# SoC.net
KiCad netlist of a schematic drawn in Altium Designer
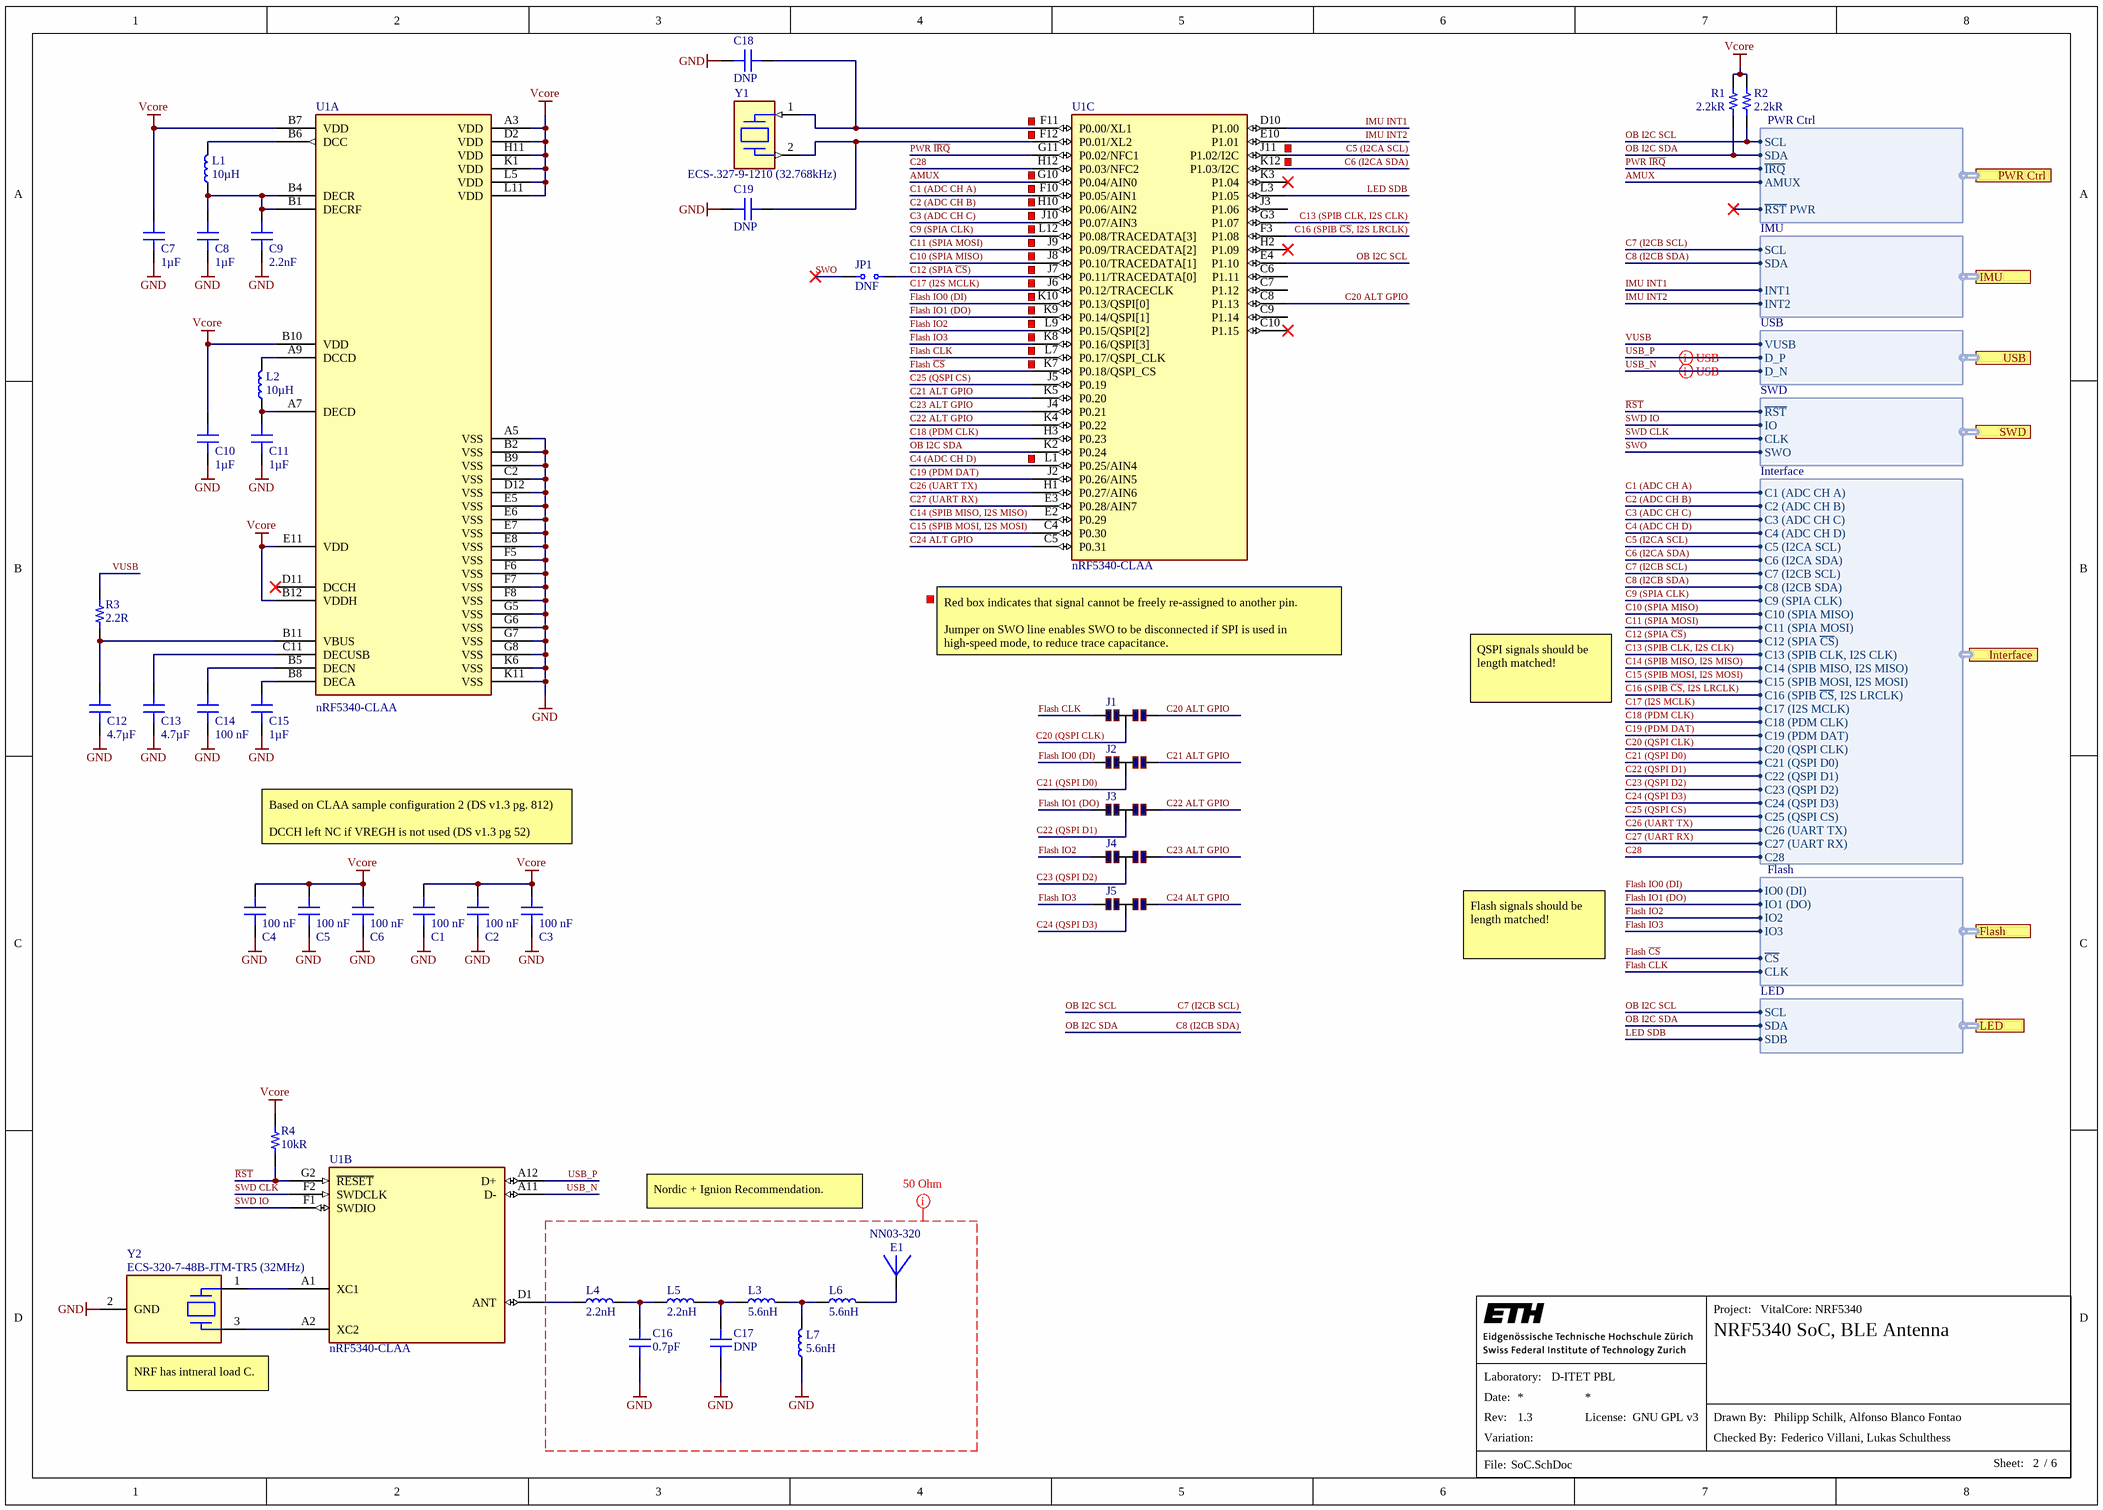
[diagram p0: SoC.SchDoc]

(export (version "E")
  (design (tool "Eeschema 10.0.6"))
  (components
    (comp (ref "C1")
      (value "100 nF")
      (footprint "VC_PCBLib:CAP_0201")
      (description "CAP CER 0.1UF 10V X5R 0201")
      (fields
        (field (name "MANUFACTURER") "Murata")
        (field (name "MANUFACTURER PART NUMBER") "GRM033Z71A104KE14D")
      )
      (libsource (lib "VC_SchematicLib") (part "CAP_0201_100n_10V"))
    )
    (comp (ref "C2")
      (value "100 nF")
      (footprint "VC_PCBLib:CAP_0201")
      (description "CAP CER 0.1UF 10V X5R 0201")
      (fields
        (field (name "MANUFACTURER") "Murata")
        (field (name "MANUFACTURER PART NUMBER") "GRM033Z71A104KE14D")
      )
      (libsource (lib "VC_SchematicLib") (part "CAP_0201_100n_10V"))
    )
    (comp (ref "C3")
      (value "100 nF")
      (footprint "VC_PCBLib:CAP_0201")
      (description "CAP CER 0.1UF 10V X5R 0201")
      (fields
        (field (name "MANUFACTURER") "Murata")
        (field (name "MANUFACTURER PART NUMBER") "GRM033Z71A104KE14D")
      )
      (libsource (lib "VC_SchematicLib") (part "CAP_0201_100n_10V"))
    )
    (comp (ref "C4")
      (value "100 nF")
      (footprint "VC_PCBLib:CAP_0201")
      (description "CAP CER 0.1UF 10V X5R 0201")
      (fields
        (field (name "MANUFACTURER") "Murata")
        (field (name "MANUFACTURER PART NUMBER") "GRM033Z71A104KE14D")
      )
      (libsource (lib "VC_SchematicLib") (part "CAP_0201_100n_10V"))
    )
    (comp (ref "C5")
      (value "100 nF")
      (footprint "VC_PCBLib:CAP_0201")
      (description "CAP CER 0.1UF 10V X5R 0201")
      (fields
        (field (name "MANUFACTURER") "Murata")
        (field (name "MANUFACTURER PART NUMBER") "GRM033Z71A104KE14D")
      )
      (libsource (lib "VC_SchematicLib") (part "CAP_0201_100n_10V"))
    )
    (comp (ref "C6")
      (value "100 nF")
      (footprint "VC_PCBLib:CAP_0201")
      (description "CAP CER 0.1UF 10V X5R 0201")
      (fields
        (field (name "MANUFACTURER") "Murata")
        (field (name "MANUFACTURER PART NUMBER") "GRM033Z71A104KE14D")
      )
      (libsource (lib "VC_SchematicLib") (part "CAP_0201_100n_10V"))
    )
    (comp (ref "C7")
      (value "1µF")
      (footprint "VC_PCBLib:CAP_0201")
      (description "CAP CER 1UF 10V X6S")
      (fields
        (field (name "MANUFACTURER") "Murata")
        (field (name "MANUFACTURER PART NUMBER") "GRM033C81A105ME05D")
      )
      (libsource (lib "VC_SchematicLib") (part "CAP_0201_1u_10V"))
    )
    (comp (ref "C8")
      (value "1µF")
      (footprint "VC_PCBLib:CAP_0201")
      (description "CAP CER 1UF 10V X6S")
      (fields
        (field (name "MANUFACTURER") "Murata")
        (field (name "MANUFACTURER PART NUMBER") "GRM033C81A105ME05D")
      )
      (libsource (lib "VC_SchematicLib") (part "CAP_0201_1u_10V"))
    )
    (comp (ref "C9")
      (value "2.2nF")
      (footprint "VC_PCBLib:CAP_0201")
      (description "CAP CER 2.2NF 16V X7R 0201")
      (fields
        (field (name "MANUFACTURER") "Murata")
        (field (name "MANUFACTURER PART NUMBER") "GRM033R71C222KA88D")
      )
      (libsource (lib "VC_SchematicLib") (part "CAP_0201_2.2n_16V"))
    )
    (comp (ref "C10")
      (value "1µF")
      (footprint "VC_PCBLib:CAP_0201")
      (description "CAP CER 1UF 10V X6S")
      (fields
        (field (name "MANUFACTURER") "Murata")
        (field (name "MANUFACTURER PART NUMBER") "GRM033C81A105ME05D")
      )
      (libsource (lib "VC_SchematicLib") (part "CAP_0201_1u_10V"))
    )
    (comp (ref "C11")
      (value "1µF")
      (footprint "VC_PCBLib:CAP_0201")
      (description "CAP CER 1UF 10V X6S")
      (fields
        (field (name "MANUFACTURER") "Murata")
        (field (name "MANUFACTURER PART NUMBER") "GRM033C81A105ME05D")
      )
      (libsource (lib "VC_SchematicLib") (part "CAP_0201_1u_10V"))
    )
    (comp (ref "C12")
      (value "4.7µF")
      (footprint "VC_PCBLib:CAP_0402")
      (description "CAP CER 4.7UF 16V X5R 0402")
      (fields
        (field (name "MANUFACTURER") "Kyocera AVX")
        (field (name "MANUFACTURER PART NUMBER") "0402YD475MAT2A")
      )
      (libsource (lib "VC_SchematicLib") (part "CAP_0402_4.7u_16V"))
    )
    (comp (ref "C13")
      (value "4.7µF")
      (footprint "VC_PCBLib:CAP_0402")
      (description "CAP CER 4.7UF 16V X5R 0402")
      (fields
        (field (name "MANUFACTURER") "Kyocera AVX")
        (field (name "MANUFACTURER PART NUMBER") "0402YD475MAT2A")
      )
      (libsource (lib "VC_SchematicLib") (part "CAP_0402_4.7u_16V"))
    )
    (comp (ref "C14")
      (value "100 nF")
      (footprint "VC_PCBLib:CAP_0201")
      (description "CAP CER 0.1UF 10V X5R 0201")
      (fields
        (field (name "MANUFACTURER") "Murata")
        (field (name "MANUFACTURER PART NUMBER") "GRM033Z71A104KE14D")
      )
      (libsource (lib "VC_SchematicLib") (part "CAP_0201_100n_10V"))
    )
    (comp (ref "C15")
      (value "1µF")
      (footprint "VC_PCBLib:CAP_0201")
      (description "CAP CER 1UF 10V X6S")
      (fields
        (field (name "MANUFACTURER") "Murata")
        (field (name "MANUFACTURER PART NUMBER") "GRM033C81A105ME05D")
      )
      (libsource (lib "VC_SchematicLib") (part "CAP_0201_1u_10V"))
    )
    (comp (ref "C16")
      (value "0.7pF")
      (footprint "VC_PCBLib:CAP_0201")
      (description "CAP RF CER 0.7PF 25V C0G 0201")
      (fields
        (field (name "MANUFACTURER") "Murata")
        (field (name "MANUFACTURER PART NUMBER") "GJM0335C1ER70BB01D")
      )
      (libsource (lib "VC_SchematicLib") (part "CAP_RF_0201_0.7pF"))
    )
    (comp (ref "C17")
      (value "DNP")
      (footprint "VC_PCBLib:CAP_0201_DNP")
      (description "CAP CER DNP 0201")
      (libsource (lib "VC_SchematicLib") (part "CAP_0201_DNP"))
    )
    (comp (ref "C18")
      (value "DNP")
      (footprint "VC_PCBLib:CAP_0201_DNP")
      (description "CAP CER DNP 0201")
      (libsource (lib "VC_SchematicLib") (part "CAP_0201_DNP"))
    )
    (comp (ref "C19")
      (value "DNP")
      (footprint "VC_PCBLib:CAP_0201_DNP")
      (description "CAP CER DNP 0201")
      (libsource (lib "VC_SchematicLib") (part "CAP_0201_DNP"))
    )
    (comp (ref "E1")
      (value "NN03-320")
      (footprint "VC_PCBLib:NN03-320")
      (description "Integrated Chip Antenna")
      (fields (field (name "MANUFACTURER") "Fractus Antennas"))
      (libsource (lib "VC_SchematicLib") (part "NN03-320"))
    )
    (comp (ref "J1")
      (value "Solder Jumper")
      (footprint "VC_PcbLib:JMP_0201_3WAY")
      (description "Solder Jumper 3 Pads")
      (fields
        (field (name "MANUFACTURER PART NUMBER") "ERJ-1GN0R00C")
        (field (name "MANUFACTURER") "Panasonic")
      )
      (libsource (lib "VC_SchematicLib") (part "JMP_0201_3WAY"))
    )
    (comp (ref "J2")
      (value "Solder Jumper")
      (footprint "VC_PcbLib:JMP_0201_3WAY")
      (description "Solder Jumper 3 Pads")
      (fields
        (field (name "MANUFACTURER PART NUMBER") "ERJ-1GN0R00C")
        (field (name "MANUFACTURER") "Panasonic")
      )
      (libsource (lib "VC_SchematicLib") (part "JMP_0201_3WAY"))
    )
    (comp (ref "J3")
      (value "Solder Jumper")
      (footprint "VC_PcbLib:JMP_0201_3WAY")
      (description "Solder Jumper 3 Pads")
      (fields
        (field (name "MANUFACTURER PART NUMBER") "ERJ-1GN0R00C")
        (field (name "MANUFACTURER") "Panasonic")
      )
      (libsource (lib "VC_SchematicLib") (part "JMP_0201_3WAY"))
    )
    (comp (ref "J4")
      (value "Solder Jumper")
      (footprint "VC_PcbLib:JMP_0201_3WAY")
      (description "Solder Jumper 3 Pads")
      (fields
        (field (name "MANUFACTURER PART NUMBER") "ERJ-1GN0R00C")
        (field (name "MANUFACTURER") "Panasonic")
      )
      (libsource (lib "VC_SchematicLib") (part "JMP_0201_3WAY"))
    )
    (comp (ref "J5")
      (value "Solder Jumper")
      (footprint "VC_PcbLib:JMP_0201_3WAY")
      (description "Solder Jumper 3 Pads")
      (fields
        (field (name "MANUFACTURER PART NUMBER") "ERJ-1GN0R00C")
        (field (name "MANUFACTURER") "Panasonic")
      )
      (libsource (lib "VC_SchematicLib") (part "JMP_0201_3WAY"))
    )
    (comp (ref "JP1")
      (value "DNF")
      (footprint "VC_PCBLib:JMP_0201")
      (description "JMP 0201 NO TRACE DNF")
      (libsource (lib "VC_SchematicLib") (part "JMP_0201_DNF"))
    )
    (comp (ref "L1")
      (value "10µH")
      (footprint "VC_PCBLib:IND_0603")
      (description "L 10uH 300mA 0603")
      (fields
        (field (name "MANUFACTURER") "Murata")
        (field (name "MANUFACTURER PART NUMBER") "LQM18DN100M70L")
      )
      (libsource (lib "VC_SchematicLib") (part "L_0603_10uH_300mA"))
    )
    (comp (ref "L2")
      (value "10µH")
      (footprint "VC_PCBLib:IND_0603")
      (description "L 10uH 300mA 0603")
      (fields
        (field (name "MANUFACTURER") "Murata")
        (field (name "MANUFACTURER PART NUMBER") "LQM18DN100M70L")
      )
      (libsource (lib "VC_SchematicLib") (part "L_0603_10uH_300mA"))
    )
    (comp (ref "L3")
      (value "5.6nH")
      (footprint "VC_PCBLib:IND_0201_MURATA_LQW03AW")
      (description "L 5.6nH RF 0201")
      (fields
        (field (name "MANUFACTURER") "Murata")
        (field (name "MANUFACTURER PART NUMBER") "LQW03AW5N6J00D")
      )
      (libsource (lib "VC_SchematicLib") (part "L_RF_0201_5.6nH"))
    )
    (comp (ref "L4")
      (value "2.2nH")
      (footprint "VC_PCBLib:IND_0201_MURATA_LQW03AW")
      (description "L 2.2nH RF 0201")
      (fields
        (field (name "MANUFACTURER") "Murata")
        (field (name "MANUFACTURER PART NUMBER") "LQP03HQ2N2B02D")
      )
      (libsource (lib "VC_SchematicLib") (part "L_RF_0201_2.2nH"))
    )
    (comp (ref "L5")
      (value "2.2nH")
      (footprint "VC_PCBLib:IND_0201_MURATA_LQW03AW")
      (description "L 2.2nH RF 0201")
      (fields
        (field (name "MANUFACTURER") "Murata")
        (field (name "MANUFACTURER PART NUMBER") "LQP03HQ2N2B02D")
      )
      (libsource (lib "VC_SchematicLib") (part "L_RF_0201_2.2nH"))
    )
    (comp (ref "L6")
      (value "5.6nH")
      (footprint "VC_PCBLib:IND_0201_MURATA_LQW03AW")
      (description "L 5.6nH RF 0201")
      (fields
        (field (name "MANUFACTURER") "Murata")
        (field (name "MANUFACTURER PART NUMBER") "LQW03AW5N6J00D")
      )
      (libsource (lib "VC_SchematicLib") (part "L_RF_0201_5.6nH"))
    )
    (comp (ref "L7")
      (value "5.6nH")
      (footprint "VC_PCBLib:IND_0201_MURATA_LQW03AW")
      (description "L 5.6nH RF 0201")
      (fields
        (field (name "MANUFACTURER") "Murata")
        (field (name "MANUFACTURER PART NUMBER") "LQW03AW5N6J00D")
      )
      (libsource (lib "VC_SchematicLib") (part "L_RF_0201_5.6nH"))
    )
    (comp (ref "R1")
      (value "2.2kR")
      (footprint "VC_PCBLib:RES_0201")
      (description "R 2.2K 1% 50mW 0201")
      (fields
        (field (name "MANUFACTURER") "Panasonic")
        (field (name "MANUFACTURER PART NUMBER") "ERJ-1GNF2201C")
      )
      (libsource (lib "VC_SchematicLib") (part "R_0201_2.2K"))
    )
    (comp (ref "R2")
      (value "2.2kR")
      (footprint "VC_PCBLib:RES_0201")
      (description "R 2.2K 1% 50mW 0201")
      (fields
        (field (name "MANUFACTURER") "Panasonic")
        (field (name "MANUFACTURER PART NUMBER") "ERJ-1GNF2201C")
      )
      (libsource (lib "VC_SchematicLib") (part "R_0201_2.2K"))
    )
    (comp (ref "R3")
      (value "2.2R")
      (footprint "VC_PCBLib:RES_0201")
      (description "R 2.2R 1% 50mW 0201")
      (fields
        (field (name "MANUFACTURER") "Yageo")
        (field (name "MANUFACTURER PART NUMBER") "RC0201FR-072R2L")
      )
      (libsource (lib "VC_SchematicLib") (part "R_0201_2.2R"))
    )
    (comp (ref "R4")
      (value "10kR")
      (footprint "VC_PCBLib:RES_0201")
      (description "R 10K 1% 50mW 0201")
      (fields
        (field (name "MANUFACTURER") "Panasonic")
        (field (name "MANUFACTURER PART NUMBER") "ERJ-1GNF1002C")
      )
      (libsource (lib "VC_SchematicLib") (part "R_0201_10K"))
    )
    (comp (ref "U1")
      (value "nRF5340-CLAA")
      (footprint "VC_PCBLib:NRF5340_WLCSP")
      (description "Multi-protocol Bluetooth Low Energy, IEEE 802.15.4, ANT and 2.4GHz proprietary system-on-chip")
      (fields
        (field (name "MANUFACTURER PART NUMBER") "NRF5340-CLAA-R7")
        (field (name "MANUFACTURER") "Nordic")
      )
      (libsource (lib "VC_SchematicLib") (part "nRF5340-CLAA"))
    )
    (comp (ref "Y1")
      (value "ECS-.327-9-1210 (32.768kHz)")
      (footprint "VC_PCBLib:Y_ECX-1210")
      (description "Crystal 32.768KHZ 9PFSMD ECX-1210 Khz Crystal 32.768KHZ 20PPM 90K Ohm -40C ~ 85C 2-SMD")
      (fields
        (field (name "MANUFACTURER") "ECS International")
        (field (name "MANUFACTURER PART NUMBER") "ECS-.327-9-1210-TR")
      )
      (libsource (lib "VC_SchematicLib") (part "Y_ECS-327-9-1210"))
    )
    (comp (ref "Y2")
      (value "ECS-320-7-48B-JTM-TR5 (32MHz)")
      (footprint "VC_PCBLib:Y_ECX-1048")
      (description "Crystal 32MHz 7pF ±20ppm ±20ppm 4-Pin Ultraminiature CSMD T/R")
      (fields
        (field (name "MANUFACTURER") "ECS International")
        (field (name "MANUFACTURER PART NUMBER") "ECS-320-7-48B-JTM-TR5")
      )
      (libsource (lib "VC_SchematicLib") (part "Y_ECS-320-7-48B-JTM-TR5"))
    )
  )
  (nets
    (net (code "9") (name "/AMUX") (class "Default")
      (node (ref "U1") (pin "G10") (pinfunction "P0.04/AIN0_G10") (pintype "bidirectional"))
    )
    (net (code "10") (name "/C1 (ADC CH A)") (class "Default")
      (node (ref "U1") (pin "F10") (pinfunction "P0.05/AIN1_F10") (pintype "bidirectional"))
    )
    (net (code "11") (name "/C2 (ADC CH B)") (class "Default")
      (node (ref "U1") (pin "H10") (pinfunction "P0.06/AIN2_H10") (pintype "bidirectional"))
    )
    (net (code "12") (name "/C3 (ADC CH C)") (class "Default")
      (node (ref "U1") (pin "J10") (pinfunction "P0.07/AIN3_J10") (pintype "bidirectional"))
    )
    (net (code "13") (name "/C4 (ADC CH D)") (class "Default")
      (node (ref "U1") (pin "L1") (pinfunction "P0.25/AIN4_L1") (pintype "bidirectional"))
    )
    (net (code "14") (name "/C5 (I2CA SCL)") (class "Default")
      (node (ref "U1") (pin "J11") (pinfunction "P1.02/I2C_J11") (pintype "bidirectional"))
    )
    (net (code "15") (name "/C6 (I2CA SDA)") (class "Default")
      (node (ref "U1") (pin "K12") (pinfunction "P1.03/I2C_K12") (pintype "bidirectional"))
    )
    (net (code "16") (name "/C7 (I2CB SCL)") (class "Default")
      (node (ref "R2") (pin "1") (pinfunction "1_1") (pintype "passive"))
      (node (ref "U1") (pin "E4") (pinfunction "P1.10_E4") (pintype "bidirectional"))
    )
    (net (code "17") (name "/C8 (I2CB SDA)") (class "Default")
      (node (ref "R1") (pin "2") (pinfunction "2_2") (pintype "passive"))
      (node (ref "U1") (pin "K2") (pinfunction "P0.24_K2") (pintype "bidirectional"))
    )
    (net (code "18") (name "/C9 (SPIA CLK)") (class "Default")
      (node (ref "U1") (pin "L12") (pinfunction "P0.08/TRACEDATA[3]_L12") (pintype "bidirectional"))
    )
    (net (code "19") (name "/C10 (SPIA MISO)") (class "Default")
      (node (ref "U1") (pin "J8") (pinfunction "P0.10/TRACEDATA[1]_J8") (pintype "bidirectional"))
    )
    (net (code "20") (name "/C11 (SPIA MOSI)") (class "Default")
      (node (ref "U1") (pin "J9") (pinfunction "P0.09/TRACEDATA[2]_J9") (pintype "bidirectional"))
    )
    (net (code "21") (name "/C12 (SPIA ~{CS})") (class "Default")
      (node (ref "JP1") (pin "2") (pinfunction "2_2") (pintype "passive"))
      (node (ref "U1") (pin "J7") (pinfunction "P0.11/TRACEDATA[0]_J7") (pintype "bidirectional"))
    )
    (net (code "22") (name "/C13 (SPIB CLK, I2S CLK)") (class "Default")
      (node (ref "U1") (pin "G3") (pinfunction "P1.07_G3") (pintype "bidirectional"))
    )
    (net (code "23") (name "/C14 (SPIB MISO, I2S MISO)") (class "Default")
      (node (ref "U1") (pin "E2") (pinfunction "P0.29_E2") (pintype "bidirectional"))
    )
    (net (code "24") (name "/C15 (SPIB MOSI, I2S MOSI)") (class "Default")
      (node (ref "U1") (pin "C4") (pinfunction "P0.30_C4") (pintype "bidirectional"))
    )
    (net (code "25") (name "/C16 (SPIB ~{CS}, I2S LRCLK)") (class "Default")
      (node (ref "U1") (pin "F3") (pinfunction "P1.08_F3") (pintype "bidirectional"))
    )
    (net (code "26") (name "/C17 (I2S MCLK)") (class "Default")
      (node (ref "U1") (pin "J6") (pinfunction "P0.12/TRACECLK_J6") (pintype "bidirectional"))
    )
    (net (code "27") (name "/C18 (PDM CLK)") (class "Default")
      (node (ref "U1") (pin "H3") (pinfunction "P0.23_H3") (pintype "bidirectional"))
    )
    (net (code "28") (name "/C19 (PDM DAT)") (class "Default")
      (node (ref "U1") (pin "J2") (pinfunction "P0.26/AIN5_J2") (pintype "bidirectional"))
    )
    (net (code "29") (name "/C20 (QSPI CLK)") (class "Default")
      (node (ref "J1") (pin "2") (pinfunction "2_2") (pintype "passive"))
    )
    (net (code "30") (name "/C20 ALT GPIO") (class "Default")
      (node (ref "J1") (pin "3") (pinfunction "3_3") (pintype "passive"))
      (node (ref "U1") (pin "C8") (pinfunction "P1.13_C8") (pintype "bidirectional"))
    )
    (net (code "31") (name "/C21 (QSPI D0)") (class "Default")
      (node (ref "J2") (pin "2") (pinfunction "2_2") (pintype "passive"))
    )
    (net (code "32") (name "/C21 ALT GPIO") (class "Default")
      (node (ref "J2") (pin "3") (pinfunction "3_3") (pintype "passive"))
      (node (ref "U1") (pin "K5") (pinfunction "P0.20_K5") (pintype "bidirectional"))
    )
    (net (code "33") (name "/C22 (QSPI D1)") (class "Default")
      (node (ref "J3") (pin "2") (pinfunction "2_2") (pintype "passive"))
    )
    (net (code "34") (name "/C22 ALT GPIO") (class "Default")
      (node (ref "J3") (pin "3") (pinfunction "3_3") (pintype "passive"))
      (node (ref "U1") (pin "K4") (pinfunction "P0.22_K4") (pintype "bidirectional"))
    )
    (net (code "35") (name "/C23 (QSPI D2)") (class "Default")
      (node (ref "J4") (pin "2") (pinfunction "2_2") (pintype "passive"))
    )
    (net (code "36") (name "/C23 ALT GPIO") (class "Default")
      (node (ref "J4") (pin "3") (pinfunction "3_3") (pintype "passive"))
      (node (ref "U1") (pin "J4") (pinfunction "P0.21_J4") (pintype "bidirectional"))
    )
    (net (code "37") (name "/C24 (QSPI D3)") (class "Default")
      (node (ref "J5") (pin "2") (pinfunction "2_2") (pintype "passive"))
    )
    (net (code "38") (name "/C24 ALT GPIO") (class "Default")
      (node (ref "J5") (pin "3") (pinfunction "3_3") (pintype "passive"))
      (node (ref "U1") (pin "C5") (pinfunction "P0.31_C5") (pintype "bidirectional"))
    )
    (net (code "39") (name "/C25 (QSPI CS)") (class "Default")
      (node (ref "U1") (pin "J5") (pinfunction "P0.19_J5") (pintype "bidirectional"))
    )
    (net (code "40") (name "/C26 (UART TX)") (class "Default")
      (node (ref "U1") (pin "H1") (pinfunction "P0.27/AIN6_H1") (pintype "bidirectional"))
    )
    (net (code "41") (name "/C27 (UART RX)") (class "Default")
      (node (ref "U1") (pin "E3") (pinfunction "P0.28/AIN7_E3") (pintype "bidirectional"))
    )
    (net (code "42") (name "/C28") (class "Default")
      (node (ref "U1") (pin "H12") (pinfunction "P0.03/NFC2_H12") (pintype "bidirectional"))
    )
    (net (code "43") (name "/Flash CLK") (class "Default")
      (node (ref "J1") (pin "1") (pinfunction "1_1") (pintype "passive"))
      (node (ref "U1") (pin "L7") (pinfunction "P0.17/QSPI_CLK_L7") (pintype "bidirectional"))
    )
    (net (code "44") (name "/Flash IO0 (DI)") (class "Default")
      (node (ref "J2") (pin "1") (pinfunction "1_1") (pintype "passive"))
      (node (ref "U1") (pin "K10") (pinfunction "P0.13/QSPI[0]_K10") (pintype "bidirectional"))
    )
    (net (code "45") (name "/Flash IO1 (DO)") (class "Default")
      (node (ref "J3") (pin "1") (pinfunction "1_1") (pintype "passive"))
      (node (ref "U1") (pin "K9") (pinfunction "P0.14/QSPI[1]_K9") (pintype "bidirectional"))
    )
    (net (code "46") (name "/Flash IO2") (class "Default")
      (node (ref "J4") (pin "1") (pinfunction "1_1") (pintype "passive"))
      (node (ref "U1") (pin "L9") (pinfunction "P0.15/QSPI[2]_L9") (pintype "bidirectional"))
    )
    (net (code "47") (name "/Flash IO3") (class "Default")
      (node (ref "J5") (pin "1") (pinfunction "1_1") (pintype "passive"))
      (node (ref "U1") (pin "K8") (pinfunction "P0.16/QSPI[3]_K8") (pintype "bidirectional"))
    )
    (net (code "48") (name "/Flash ~{CS}") (class "Default")
      (node (ref "U1") (pin "K7") (pinfunction "P0.18/QSPI_CS_K7") (pintype "bidirectional"))
    )
    (net (code "49") (name "/IMU INT1") (class "Default")
      (node (ref "U1") (pin "D10") (pinfunction "P1.00_D10") (pintype "bidirectional"))
    )
    (net (code "50") (name "/IMU INT2") (class "Default")
      (node (ref "U1") (pin "E10") (pinfunction "P1.01_E10") (pintype "bidirectional"))
    )
    (net (code "51") (name "/LED SDB") (class "Default")
      (node (ref "U1") (pin "L3") (pinfunction "P1.05_L3") (pintype "bidirectional"))
    )
    (net (code "52") (name "/PWR ~{IRQ}") (class "Default")
      (node (ref "U1") (pin "G11") (pinfunction "P0.02/NFC1_G11") (pintype "bidirectional"))
    )
    (net (code "53") (name "/SWD CLK") (class "Default")
      (node (ref "U1") (pin "F2") (pinfunction "SWDCLK_F2") (pintype "input"))
    )
    (net (code "54") (name "/SWD IO") (class "Default")
      (node (ref "U1") (pin "F1") (pinfunction "SWDIO_F1") (pintype "bidirectional"))
    )
    (net (code "55") (name "/SWO") (class "Default")
      (node (ref "JP1") (pin "1") (pinfunction "1_1") (pintype "passive"))
    )
    (net (code "56") (name "/USB_N") (class "Default")
      (node (ref "U1") (pin "A11") (pinfunction "D-_A11") (pintype "bidirectional"))
    )
    (net (code "57") (name "/USB_P") (class "Default")
      (node (ref "U1") (pin "A12") (pinfunction "D+_A12") (pintype "bidirectional"))
    )
    (net (code "58") (name "/VUSB") (class "Default")
      (node (ref "R3") (pin "1") (pinfunction "1_1") (pintype "passive"))
    )
    (net (code "66") (name "/~{RST}") (class "Default")
      (node (ref "R4") (pin "1") (pinfunction "1_1") (pintype "passive"))
      (node (ref "U1") (pin "G2") (pinfunction "~{RESET}_G2") (pintype "input"))
    )
    (net (code "67") (name "GND") (class "Default")
      (node (ref "C1") (pin "1") (pinfunction "1_1") (pintype "passive"))
      (node (ref "C10") (pin "1") (pinfunction "1_1") (pintype "passive"))
      (node (ref "C11") (pin "1") (pinfunction "1_1") (pintype "passive"))
      (node (ref "C12") (pin "1") (pinfunction "1_1") (pintype "passive"))
      (node (ref "C13") (pin "1") (pinfunction "1_1") (pintype "passive"))
      (node (ref "C14") (pin "1") (pinfunction "1_1") (pintype "passive"))
      (node (ref "C15") (pin "1") (pinfunction "1_1") (pintype "passive"))
      (node (ref "C16") (pin "1") (pinfunction "1_1") (pintype "passive"))
      (node (ref "C17") (pin "1") (pinfunction "1_1") (pintype "passive"))
      (node (ref "C18") (pin "1") (pinfunction "1_1") (pintype "passive"))
      (node (ref "C19") (pin "1") (pinfunction "1_1") (pintype "passive"))
      (node (ref "C2") (pin "1") (pinfunction "1_1") (pintype "passive"))
      (node (ref "C3") (pin "1") (pinfunction "1_1") (pintype "passive"))
      (node (ref "C4") (pin "1") (pinfunction "1_1") (pintype "passive"))
      (node (ref "C5") (pin "1") (pinfunction "1_1") (pintype "passive"))
      (node (ref "C6") (pin "1") (pinfunction "1_1") (pintype "passive"))
      (node (ref "C7") (pin "1") (pinfunction "1_1") (pintype "passive"))
      (node (ref "C8") (pin "1") (pinfunction "1_1") (pintype "passive"))
      (node (ref "C9") (pin "1") (pinfunction "1_1") (pintype "passive"))
      (node (ref "L7") (pin "1") (pinfunction "1_1") (pintype "passive"))
      (node (ref "U1") (pin "A5") (pinfunction "VSS_A5") (pintype "power_in"))
      (node (ref "U1") (pin "B2") (pinfunction "VSS_B2") (pintype "power_in"))
      (node (ref "U1") (pin "B9") (pinfunction "VSS_B9") (pintype "power_in"))
      (node (ref "U1") (pin "C2") (pinfunction "VSS_C2") (pintype "power_in"))
      (node (ref "U1") (pin "D12") (pinfunction "VSS_D12") (pintype "power_in"))
      (node (ref "U1") (pin "E5") (pinfunction "VSS_E5") (pintype "power_in"))
      (node (ref "U1") (pin "E6") (pinfunction "VSS_E6") (pintype "power_in"))
      (node (ref "U1") (pin "E7") (pinfunction "VSS_E7") (pintype "power_in"))
      (node (ref "U1") (pin "E8") (pinfunction "VSS_E8") (pintype "power_in"))
      (node (ref "U1") (pin "F5") (pinfunction "VSS_F5") (pintype "power_in"))
      (node (ref "U1") (pin "F6") (pinfunction "VSS_F6") (pintype "power_in"))
      (node (ref "U1") (pin "F7") (pinfunction "VSS_F7") (pintype "power_in"))
      (node (ref "U1") (pin "F8") (pinfunction "VSS_F8") (pintype "power_in"))
      (node (ref "U1") (pin "G5") (pinfunction "VSS_G5") (pintype "power_in"))
      (node (ref "U1") (pin "G6") (pinfunction "VSS_G6") (pintype "power_in"))
      (node (ref "U1") (pin "G7") (pinfunction "VSS_G7") (pintype "power_in"))
      (node (ref "U1") (pin "G8") (pinfunction "VSS_G8") (pintype "power_in"))
      (node (ref "U1") (pin "K11") (pinfunction "VSS_K11") (pintype "power_in"))
      (node (ref "U1") (pin "K6") (pinfunction "VSS_K6") (pintype "power_in"))
      (node (ref "Y2") (pin "2") (pinfunction "GND_2") (pintype "power_in"))
    )
    (net (code "68") (name "Net-(C16-Pad2)") (class "Default")
      (node (ref "C16") (pin "2") (pinfunction "2_2") (pintype "passive"))
      (node (ref "L4") (pin "2") (pinfunction "2_2") (pintype "passive"))
      (node (ref "L5") (pin "1") (pinfunction "1_1") (pintype "passive"))
    )
    (net (code "69") (name "Net-(C17-Pad2)") (class "Default")
      (node (ref "C17") (pin "2") (pinfunction "2_2") (pintype "passive"))
      (node (ref "L3") (pin "1") (pinfunction "1_1") (pintype "passive"))
      (node (ref "L5") (pin "2") (pinfunction "2_2") (pintype "passive"))
    )
    (net (code "70") (name "Net-(E1-Pad1)") (class "Default")
      (node (ref "E1") (pin "1") (pinfunction "1_1") (pintype "passive"))
      (node (ref "L6") (pin "2") (pinfunction "2_2") (pintype "passive"))
    )
    (net (code "71") (name "Net-(L3-Pad2)") (class "Default")
      (node (ref "L3") (pin "2") (pinfunction "2_2") (pintype "passive"))
      (node (ref "L6") (pin "1") (pinfunction "1_1") (pintype "passive"))
      (node (ref "L7") (pin "2") (pinfunction "2_2") (pintype "passive"))
    )
    (net (code "72") (name "Net-(U1A-DCC)") (class "Default")
      (node (ref "L1") (pin "2") (pinfunction "2_2") (pintype "passive"))
      (node (ref "U1") (pin "B6") (pinfunction "DCC_B6") (pintype "output"))
    )
    (net (code "73") (name "Net-(U1A-DCCD)") (class "Default")
      (node (ref "L2") (pin "2") (pinfunction "2_2") (pintype "passive"))
      (node (ref "U1") (pin "A9") (pinfunction "DCCD_A9") (pintype "power_in"))
    )
    (net (code "74") (name "Net-(U1A-DECA)") (class "Default")
      (node (ref "C15") (pin "2") (pinfunction "2_2") (pintype "passive"))
      (node (ref "U1") (pin "B8") (pinfunction "DECA_B8") (pintype "power_in"))
    )
    (net (code "75") (name "Net-(U1A-DECD)") (class "Default")
      (node (ref "C11") (pin "2") (pinfunction "2_2") (pintype "passive"))
      (node (ref "L2") (pin "1") (pinfunction "1_1") (pintype "passive"))
      (node (ref "U1") (pin "A7") (pinfunction "DECD_A7") (pintype "power_in"))
    )
    (net (code "76") (name "Net-(U1A-DECN)") (class "Default")
      (node (ref "C14") (pin "2") (pinfunction "2_2") (pintype "passive"))
      (node (ref "U1") (pin "B5") (pinfunction "DECN_B5") (pintype "power_in"))
    )
    (net (code "77") (name "Net-(U1A-DECR)") (class "Default")
      (node (ref "C8") (pin "2") (pinfunction "2_2") (pintype "passive"))
      (node (ref "C9") (pin "2") (pinfunction "2_2") (pintype "passive"))
      (node (ref "L1") (pin "1") (pinfunction "1_1") (pintype "passive"))
      (node (ref "U1") (pin "B1") (pinfunction "DECRF_B1") (pintype "power_in"))
      (node (ref "U1") (pin "B4") (pinfunction "DECR_B4") (pintype "power_in"))
    )
    (net (code "78") (name "Net-(U1A-DECUSB)") (class "Default")
      (node (ref "C13") (pin "2") (pinfunction "2_2") (pintype "passive"))
      (node (ref "U1") (pin "C11") (pinfunction "DECUSB_C11") (pintype "power_in"))
    )
    (net (code "79") (name "Net-(U1A-VBUS)") (class "Default")
      (node (ref "C12") (pin "2") (pinfunction "2_2") (pintype "passive"))
      (node (ref "R3") (pin "2") (pinfunction "2_2") (pintype "passive"))
      (node (ref "U1") (pin "B11") (pinfunction "VBUS_B11") (pintype "power_in"))
    )
    (net (code "80") (name "Net-(U1B-ANT)") (class "Default")
      (node (ref "L4") (pin "1") (pinfunction "1_1") (pintype "passive"))
      (node (ref "U1") (pin "D1") (pinfunction "ANT_D1") (pintype "bidirectional"))
    )
    (net (code "81") (name "Net-(U1B-XC1)") (class "Default")
      (node (ref "U1") (pin "A1") (pinfunction "XC1_A1") (pintype "passive"))
      (node (ref "Y2") (pin "1") (pinfunction "1_1") (pintype "passive"))
    )
    (net (code "82") (name "Net-(U1B-XC2)") (class "Default")
      (node (ref "U1") (pin "A2") (pinfunction "XC2_A2") (pintype "passive"))
      (node (ref "Y2") (pin "3") (pinfunction "3_3") (pintype "passive"))
    )
    (net (code "83") (name "Net-(U1C-P0.00{slash}XL1)") (class "Default")
      (node (ref "C18") (pin "2") (pinfunction "2_2") (pintype "passive"))
      (node (ref "U1") (pin "F11") (pinfunction "P0.00/XL1_F11") (pintype "bidirectional"))
      (node (ref "Y1") (pin "1") (pinfunction "1_1") (pintype "input"))
    )
    (net (code "84") (name "Net-(U1C-P0.01{slash}XL2)") (class "Default")
      (node (ref "C19") (pin "2") (pinfunction "2_2") (pintype "passive"))
      (node (ref "U1") (pin "F12") (pinfunction "P0.01/XL2_F12") (pintype "bidirectional"))
      (node (ref "Y1") (pin "2") (pinfunction "2_2") (pintype "output"))
    )
    (net (code "85") (name "Vcore") (class "Default")
      (node (ref "C1") (pin "2") (pinfunction "2_2") (pintype "passive"))
      (node (ref "C10") (pin "2") (pinfunction "2_2") (pintype "passive"))
      (node (ref "C2") (pin "2") (pinfunction "2_2") (pintype "passive"))
      (node (ref "C3") (pin "2") (pinfunction "2_2") (pintype "passive"))
      (node (ref "C4") (pin "2") (pinfunction "2_2") (pintype "passive"))
      (node (ref "C5") (pin "2") (pinfunction "2_2") (pintype "passive"))
      (node (ref "C6") (pin "2") (pinfunction "2_2") (pintype "passive"))
      (node (ref "C7") (pin "2") (pinfunction "2_2") (pintype "passive"))
      (node (ref "R1") (pin "1") (pinfunction "1_1") (pintype "passive"))
      (node (ref "R2") (pin "2") (pinfunction "2_2") (pintype "passive"))
      (node (ref "R4") (pin "2") (pinfunction "2_2") (pintype "passive"))
      (node (ref "U1") (pin "A3") (pinfunction "VDD_A3") (pintype "power_in"))
      (node (ref "U1") (pin "B10") (pinfunction "VDD_B10") (pintype "power_in"))
      (node (ref "U1") (pin "B12") (pinfunction "VDDH_B12") (pintype "power_in"))
      (node (ref "U1") (pin "B7") (pinfunction "VDD_B7") (pintype "power_in"))
      (node (ref "U1") (pin "D2") (pinfunction "VDD_D2") (pintype "power_in"))
      (node (ref "U1") (pin "E11") (pinfunction "VDD_E11") (pintype "power_in"))
      (node (ref "U1") (pin "H11") (pinfunction "VDD_H11") (pintype "power_in"))
      (node (ref "U1") (pin "K1") (pinfunction "VDD_K1") (pintype "power_in"))
      (node (ref "U1") (pin "L11") (pinfunction "VDD_L11") (pintype "power_in"))
      (node (ref "U1") (pin "L5") (pinfunction "VDD_L5") (pintype "power_in"))
    )
    (net (code "86") (name "unconnected-(U1A-DCCH-PadD11)") (class "Default")
      (node (ref "U1") (pin "D11") (pinfunction "DCCH_D11") (pintype "power_in+no_connect"))
    )
    (net (code "87") (name "unconnected-(U1C-P1.04-PadK3)") (class "Default")
      (node (ref "U1") (pin "K3") (pinfunction "P1.04_K3") (pintype "bidirectional+no_connect"))
    )
    (net (code "88") (name "unconnected-(U1C-P1.06-PadJ3)") (class "Default")
      (node (ref "U1") (pin "J3") (pinfunction "P1.06_J3") (pintype "bidirectional"))
    )
    (net (code "89") (name "unconnected-(U1C-P1.09-PadH2)") (class "Default")
      (node (ref "U1") (pin "H2") (pinfunction "P1.09_H2") (pintype "bidirectional+no_connect"))
    )
    (net (code "90") (name "unconnected-(U1C-P1.11-PadC6)") (class "Default")
      (node (ref "U1") (pin "C6") (pinfunction "P1.11_C6") (pintype "bidirectional"))
    )
    (net (code "91") (name "unconnected-(U1C-P1.12-PadC7)") (class "Default")
      (node (ref "U1") (pin "C7") (pinfunction "P1.12_C7") (pintype "bidirectional"))
    )
    (net (code "92") (name "unconnected-(U1C-P1.14-PadC9)") (class "Default")
      (node (ref "U1") (pin "C9") (pinfunction "P1.14_C9") (pintype "bidirectional"))
    )
    (net (code "93") (name "unconnected-(U1C-P1.15-PadC10)") (class "Default")
      (node (ref "U1") (pin "C10") (pinfunction "P1.15_C10") (pintype "bidirectional+no_connect"))
    )
  )
)
